# pc_pulse_Express.net
KiCad netlist of a schematic drawn in EAGLE
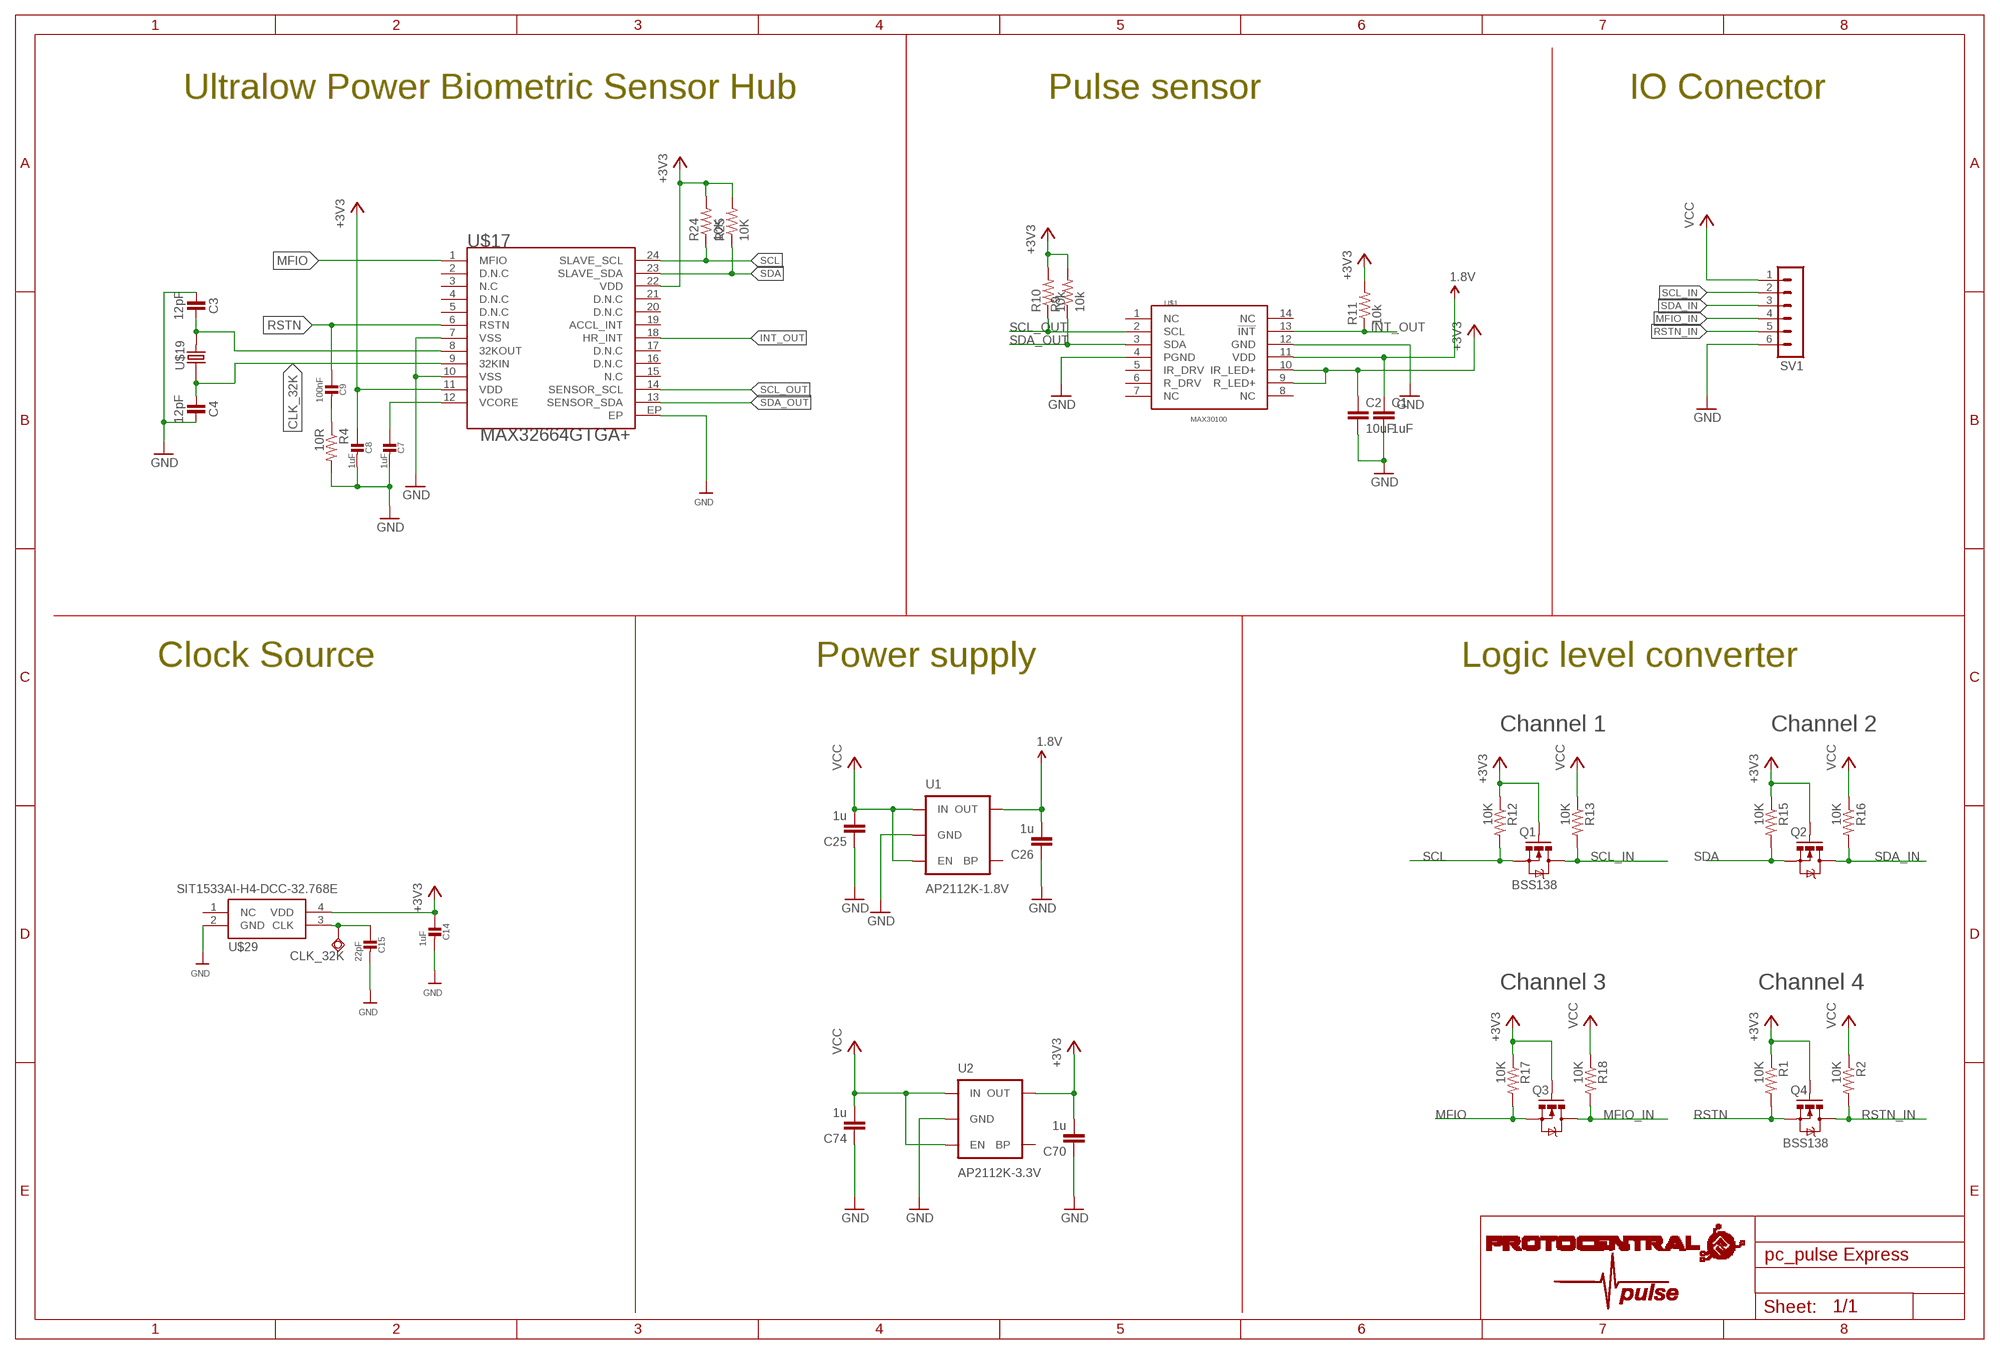
[diagram p0: schematic, sheet 1]

(export (version "E")
  (design (tool "Eeschema 10.0.6"))
  (components
    (comp (ref "C1")
      (value "1uF")
      (footprint "eagle-import:C0402")
      (libsource (lib "eagle-import") (part "rcl_334_C-EUC0402"))
    )
    (comp (ref "C2")
      (value "10uF")
      (footprint "eagle-import:C0402")
      (libsource (lib "eagle-import") (part "rcl_334_C-EUC0402"))
    )
    (comp (ref "C3")
      (value "12pF")
      (footprint "eagle-import:C0402")
      (libsource (lib "eagle-import") (part "CAPACITORS-0402"))
    )
    (comp (ref "C4")
      (value "12pF")
      (footprint "eagle-import:C0402")
      (libsource (lib "eagle-import") (part "CAPACITORS-0402"))
    )
    (comp (ref "C7")
      (value "1uF")
      (footprint "eagle-import:_0402")
      (libsource (lib "eagle-import") (part "CAP_CERAMIC_0402"))
    )
    (comp (ref "C8")
      (value "1uF")
      (footprint "eagle-import:_0402")
      (libsource (lib "eagle-import") (part "CAP_CERAMIC_0402"))
    )
    (comp (ref "C9")
      (value "100nF")
      (footprint "eagle-import:_0402")
      (libsource (lib "eagle-import") (part "CAP_CERAMIC_0402"))
    )
    (comp (ref "C14")
      (value "1uF")
      (footprint "eagle-import:_0402")
      (libsource (lib "eagle-import") (part "CAP_CERAMIC_0402"))
    )
    (comp (ref "C15")
      (value "22pF")
      (footprint "eagle-import:_0402")
      (libsource (lib "eagle-import") (part "CAP_CERAMIC_0402"))
    )
    (comp (ref "C25")
      (value "1u")
      (footprint "eagle-import:C0402")
      (libsource (lib "eagle-import") (part "rcl_334_C-EUC0402"))
    )
    (comp (ref "C26")
      (value "1u")
      (footprint "eagle-import:C0402")
      (libsource (lib "eagle-import") (part "rcl_334_C-EUC0402"))
    )
    (comp (ref "C70")
      (value "1u")
      (footprint "eagle-import:C0402")
      (libsource (lib "eagle-import") (part "C-EUC0402"))
    )
    (comp (ref "C74")
      (value "1u")
      (footprint "eagle-import:C0402")
      (libsource (lib "eagle-import") (part "C-EUC0402"))
    )
    (comp (ref "Q1")
      (value "BSS138")
      (footprint "eagle-import:SOT23-3")
      (libsource (lib "eagle-import") (part "MOSFET-NCHANNELSMD"))
    )
    (comp (ref "Q2")
      (value "BSS138")
      (footprint "eagle-import:SOT23-3")
      (libsource (lib "eagle-import") (part "MOSFET-NCHANNELSMD"))
    )
    (comp (ref "Q3")
      (value "BSS138")
      (footprint "eagle-import:SOT23-3")
      (libsource (lib "eagle-import") (part "MOSFET-NCHANNELSMD"))
    )
    (comp (ref "Q4")
      (value "BSS138")
      (footprint "eagle-import:SOT23-3")
      (libsource (lib "eagle-import") (part "MOSFET-NCHANNELSMD"))
    )
    (comp (ref "R1")
      (value "10K")
      (footprint "eagle-import:0402-RES")
      (libsource (lib "eagle-import") (part "RESISTOR0402-RES"))
    )
    (comp (ref "R2")
      (value "10K")
      (footprint "eagle-import:0402-RES")
      (libsource (lib "eagle-import") (part "RESISTOR0402-RES"))
    )
    (comp (ref "R4")
      (value "10R")
      (footprint "eagle-import:0402-RES")
      (libsource (lib "eagle-import") (part "RESISTOR0402-RES"))
    )
    (comp (ref "R9")
      (value "10k")
      (footprint "eagle-import:R0402")
      (libsource (lib "eagle-import") (part "R-US_R0402"))
    )
    (comp (ref "R10")
      (value "10k")
      (footprint "eagle-import:R0402")
      (libsource (lib "eagle-import") (part "R-US_R0402"))
    )
    (comp (ref "R11")
      (value "10k")
      (footprint "eagle-import:R0402")
      (libsource (lib "eagle-import") (part "R-US_R0402"))
    )
    (comp (ref "R12")
      (value "10K")
      (footprint "eagle-import:0402-RES")
      (libsource (lib "eagle-import") (part "RESISTOR0402-RES"))
    )
    (comp (ref "R13")
      (value "10K")
      (footprint "eagle-import:0402-RES")
      (libsource (lib "eagle-import") (part "RESISTOR0402-RES"))
    )
    (comp (ref "R15")
      (value "10K")
      (footprint "eagle-import:0402-RES")
      (libsource (lib "eagle-import") (part "RESISTOR0402-RES"))
    )
    (comp (ref "R16")
      (value "10K")
      (footprint "eagle-import:0402-RES")
      (libsource (lib "eagle-import") (part "RESISTOR0402-RES"))
    )
    (comp (ref "R17")
      (value "10K")
      (footprint "eagle-import:0402-RES")
      (libsource (lib "eagle-import") (part "RESISTOR0402-RES"))
    )
    (comp (ref "R18")
      (value "10K")
      (footprint "eagle-import:0402-RES")
      (libsource (lib "eagle-import") (part "RESISTOR0402-RES"))
    )
    (comp (ref "R24")
      (value "10K")
      (footprint "eagle-import:0402-RES")
      (libsource (lib "eagle-import") (part "RESISTOR0402-RES"))
    )
    (comp (ref "R25")
      (value "10K")
      (footprint "eagle-import:0402-RES")
      (libsource (lib "eagle-import") (part "RESISTOR0402-RES"))
    )
    (comp (ref "SV1")
      (value "MA06-1")
      (footprint "eagle-import:MA06-1")
      (libsource (lib "eagle-import") (part "MA06-1"))
    )
    (comp (ref "SWIO1")
      (value "TPSQTP11R")
      (footprint "eagle-import:TP11R")
      (libsource (lib "eagle-import") (part "TPSQTP11R"))
    )
    (comp (ref "U$1")
      (value "MAX30100")
      (footprint "eagle-import:OESIP-14")
      (libsource (lib "eagle-import") (part "MAX30100"))
    )
    (comp (ref "U$3")
      (value "PROTY_LOGO_WITH_TEXT")
      (footprint "eagle-import:PROTY_WITH_TEXT")
      (libsource (lib "eagle-import") (part "PROTY_LOGO_WITH_TEXT"))
    )
    (comp (ref "U$4")
      (value "PULSE")
      (footprint "eagle-import:PULSESMALL")
      (libsource (lib "eagle-import") (part "PULSE"))
    )
    (comp (ref "U$17")
      (value "MAX32664GTGA+")
      (footprint "eagle-import:TQFN-24L")
      (libsource (lib "eagle-import") (part "MAX32664GTGA+"))
    )
    (comp (ref "U$19")
      (value "520-327-12.5-34B(32.768KHZ)")
      (footprint "eagle-import:ECX-31B")
      (libsource (lib "eagle-import") (part "ECS-X-34B"))
    )
    (comp (ref "U$29")
      (value "SIT1533AI-H4-DCC-32.768E")
      (footprint "eagle-import:SIT1533")
      (libsource (lib "eagle-import") (part "SIT1533AI-H4-DCC-32.768E"))
    )
    (comp (ref "U1")
      (value "AP2112K-1.8V")
      (footprint "eagle-import:SOT23-5")
      (libsource (lib "eagle-import") (part "V_REG_LDOSMD"))
    )
    (comp (ref "U2")
      (value "AP2112K-3.3V")
      (footprint "eagle-import:SOT23-5")
      (libsource (lib "eagle-import") (part "V_REG_LDOSMD"))
    )
  )
  (nets
    (net (code "1") (name "+3V3") (class "Default")
      (node (ref "C14") (pin "1") (pinfunction "1_1") (pintype "passive"))
      (node (ref "C2") (pin "1") (pinfunction "1_1") (pintype "passive"))
      (node (ref "C70") (pin "2") (pinfunction "2_2") (pintype "passive"))
      (node (ref "C8") (pin "1") (pinfunction "1_1") (pintype "passive"))
      (node (ref "Q1") (pin "1") (pinfunction "G_1") (pintype "passive"))
      (node (ref "Q2") (pin "1") (pinfunction "G_1") (pintype "passive"))
      (node (ref "Q3") (pin "1") (pinfunction "G_1") (pintype "passive"))
      (node (ref "Q4") (pin "1") (pinfunction "G_1") (pintype "passive"))
      (node (ref "R1") (pin "1") (pinfunction "1_1") (pintype "passive"))
      (node (ref "R10") (pin "2") (pinfunction "2_2") (pintype "passive"))
      (node (ref "R11") (pin "2") (pinfunction "2_2") (pintype "passive"))
      (node (ref "R12") (pin "1") (pinfunction "1_1") (pintype "passive"))
      (node (ref "R15") (pin "1") (pinfunction "1_1") (pintype "passive"))
      (node (ref "R17") (pin "1") (pinfunction "1_1") (pintype "passive"))
      (node (ref "R24") (pin "2") (pinfunction "2_2") (pintype "passive"))
      (node (ref "R25") (pin "2") (pinfunction "2_2") (pintype "passive"))
      (node (ref "R9") (pin "2") (pinfunction "2_2") (pintype "passive"))
      (node (ref "U$1") (pin "10") (pinfunction "IR_LED+_10") (pintype "bidirectional"))
      (node (ref "U$1") (pin "9") (pinfunction "R_LED+_9") (pintype "bidirectional"))
      (node (ref "U$17") (pin "11") (pinfunction "VDD_11") (pintype "bidirectional"))
      (node (ref "U$17") (pin "22") (pinfunction "VDD_22") (pintype "bidirectional"))
      (node (ref "U$29") (pin "4") (pinfunction "VDD_4") (pintype "bidirectional"))
      (node (ref "U2") (pin "5") (pinfunction "OUT_5") (pintype "passive"))
    )
    (net (code "2") (name "1.8V") (class "Default")
      (node (ref "C1") (pin "1") (pinfunction "1_1") (pintype "passive"))
      (node (ref "C26") (pin "2") (pinfunction "2_2") (pintype "passive"))
      (node (ref "U$1") (pin "11") (pinfunction "VDD_11") (pintype "bidirectional"))
      (node (ref "U1") (pin "5") (pinfunction "OUT_5") (pintype "passive"))
    )
    (net (code "3") (name "CLK_32K") (class "Default")
      (node (ref "C15") (pin "1") (pinfunction "1_1") (pintype "passive"))
      (node (ref "C4") (pin "1") (pinfunction "1_1") (pintype "passive"))
      (node (ref "SWIO1") (pin "TP") (pinfunction "TP_TP") (pintype "input"))
      (node (ref "U$17") (pin "9") (pinfunction "32KIN_9") (pintype "bidirectional"))
      (node (ref "U$19") (pin "P$1") (pinfunction "1_P$1") (pintype "passive"))
      (node (ref "U$29") (pin "3") (pinfunction "CLK_3") (pintype "bidirectional"))
    )
    (net (code "4") (name "GND") (class "Default")
      (node (ref "C1") (pin "2") (pinfunction "2_2") (pintype "passive"))
      (node (ref "C14") (pin "2") (pinfunction "2_2") (pintype "passive"))
      (node (ref "C15") (pin "2") (pinfunction "2_2") (pintype "passive"))
      (node (ref "C2") (pin "2") (pinfunction "2_2") (pintype "passive"))
      (node (ref "C25") (pin "1") (pinfunction "1_1") (pintype "passive"))
      (node (ref "C26") (pin "1") (pinfunction "1_1") (pintype "passive"))
      (node (ref "C3") (pin "1") (pinfunction "1_1") (pintype "passive"))
      (node (ref "C4") (pin "2") (pinfunction "2_2") (pintype "passive"))
      (node (ref "C7") (pin "2") (pinfunction "2_2") (pintype "passive"))
      (node (ref "C70") (pin "1") (pinfunction "1_1") (pintype "passive"))
      (node (ref "C74") (pin "1") (pinfunction "1_1") (pintype "passive"))
      (node (ref "C8") (pin "2") (pinfunction "2_2") (pintype "passive"))
      (node (ref "R4") (pin "2") (pinfunction "2_2") (pintype "passive"))
      (node (ref "SV1") (pin "6") (pinfunction "6_6") (pintype "passive"))
      (node (ref "U$1") (pin "12") (pinfunction "GND_12") (pintype "bidirectional"))
      (node (ref "U$1") (pin "4") (pinfunction "PGND_4") (pintype "bidirectional"))
      (node (ref "U$17") (pin "10") (pinfunction "VSS_10") (pintype "bidirectional"))
      (node (ref "U$17") (pin "7") (pinfunction "VSS_7") (pintype "bidirectional"))
      (node (ref "U$17") (pin "EP") (pinfunction "EP_EP") (pintype "bidirectional"))
      (node (ref "U$29") (pin "2") (pinfunction "GND_2") (pintype "bidirectional"))
      (node (ref "U1") (pin "2") (pinfunction "GND_2") (pintype "input"))
      (node (ref "U2") (pin "2") (pinfunction "GND_2") (pintype "input"))
    )
    (net (code "5") (name "INT_OUT") (class "Default")
      (node (ref "R11") (pin "1") (pinfunction "1_1") (pintype "passive"))
      (node (ref "U$1") (pin "13") (pinfunction "~{INT}_13") (pintype "bidirectional"))
      (node (ref "U$17") (pin "18") (pinfunction "HR_INT_18") (pintype "bidirectional"))
    )
    (net (code "6") (name "MFIO") (class "Default")
      (node (ref "Q3") (pin "2") (pinfunction "S_2") (pintype "passive"))
      (node (ref "R17") (pin "2") (pinfunction "2_2") (pintype "passive"))
      (node (ref "U$17") (pin "1") (pinfunction "MFIO_1") (pintype "bidirectional"))
    )
    (net (code "7") (name "MFIO_IN") (class "Default")
      (node (ref "Q3") (pin "3") (pinfunction "D_3") (pintype "passive"))
      (node (ref "R18") (pin "2") (pinfunction "2_2") (pintype "passive"))
      (node (ref "SV1") (pin "4") (pinfunction "4_4") (pintype "passive"))
    )
    (net (code "8") (name "Net-(C9-Pad2)") (class "Default")
      (node (ref "C9") (pin "2") (pinfunction "2_2") (pintype "passive"))
      (node (ref "R4") (pin "1") (pinfunction "1_1") (pintype "passive"))
    )
    (net (code "9") (name "Net-(U$17-32KOUT)") (class "Default")
      (node (ref "C3") (pin "2") (pinfunction "2_2") (pintype "passive"))
      (node (ref "U$17") (pin "8") (pinfunction "32KOUT_8") (pintype "bidirectional"))
      (node (ref "U$19") (pin "P$2") (pinfunction "2_P$2") (pintype "passive"))
    )
    (net (code "10") (name "Net-(U$17-VCORE)") (class "Default")
      (node (ref "C7") (pin "1") (pinfunction "1_1") (pintype "passive"))
      (node (ref "U$17") (pin "12") (pinfunction "VCORE_12") (pintype "bidirectional"))
    )
    (net (code "11") (name "RSTN") (class "Default")
      (node (ref "C9") (pin "1") (pinfunction "1_1") (pintype "passive"))
      (node (ref "Q4") (pin "2") (pinfunction "S_2") (pintype "passive"))
      (node (ref "R1") (pin "2") (pinfunction "2_2") (pintype "passive"))
      (node (ref "U$17") (pin "6") (pinfunction "RSTN_6") (pintype "bidirectional"))
    )
    (net (code "12") (name "RSTN_IN") (class "Default")
      (node (ref "Q4") (pin "3") (pinfunction "D_3") (pintype "passive"))
      (node (ref "R2") (pin "2") (pinfunction "2_2") (pintype "passive"))
      (node (ref "SV1") (pin "5") (pinfunction "5_5") (pintype "passive"))
    )
    (net (code "13") (name "SCL") (class "Default")
      (node (ref "Q1") (pin "2") (pinfunction "S_2") (pintype "passive"))
      (node (ref "R12") (pin "2") (pinfunction "2_2") (pintype "passive"))
      (node (ref "R24") (pin "1") (pinfunction "1_1") (pintype "passive"))
      (node (ref "U$17") (pin "24") (pinfunction "SLAVE_SCL_24") (pintype "bidirectional"))
    )
    (net (code "14") (name "SCL_IN") (class "Default")
      (node (ref "Q1") (pin "3") (pinfunction "D_3") (pintype "passive"))
      (node (ref "R13") (pin "2") (pinfunction "2_2") (pintype "passive"))
      (node (ref "SV1") (pin "2") (pinfunction "2_2") (pintype "passive"))
    )
    (net (code "15") (name "SCL_OUT") (class "Default")
      (node (ref "R10") (pin "1") (pinfunction "1_1") (pintype "passive"))
      (node (ref "U$1") (pin "2") (pinfunction "SCL_2") (pintype "bidirectional"))
      (node (ref "U$17") (pin "14") (pinfunction "SENSOR_SCL_14") (pintype "bidirectional"))
    )
    (net (code "16") (name "SDA") (class "Default")
      (node (ref "Q2") (pin "2") (pinfunction "S_2") (pintype "passive"))
      (node (ref "R15") (pin "2") (pinfunction "2_2") (pintype "passive"))
      (node (ref "R25") (pin "1") (pinfunction "1_1") (pintype "passive"))
      (node (ref "U$17") (pin "23") (pinfunction "SLAVE_SDA_23") (pintype "bidirectional"))
    )
    (net (code "17") (name "SDA_IN") (class "Default")
      (node (ref "Q2") (pin "3") (pinfunction "D_3") (pintype "passive"))
      (node (ref "R16") (pin "2") (pinfunction "2_2") (pintype "passive"))
      (node (ref "SV1") (pin "3") (pinfunction "3_3") (pintype "passive"))
    )
    (net (code "18") (name "SDA_OUT") (class "Default")
      (node (ref "R9") (pin "1") (pinfunction "1_1") (pintype "passive"))
      (node (ref "U$1") (pin "3") (pinfunction "SDA_3") (pintype "bidirectional"))
      (node (ref "U$17") (pin "13") (pinfunction "SENSOR_SDA_13") (pintype "bidirectional"))
    )
    (net (code "19") (name "VCC") (class "Default")
      (node (ref "C25") (pin "2") (pinfunction "2_2") (pintype "passive"))
      (node (ref "C74") (pin "2") (pinfunction "2_2") (pintype "passive"))
      (node (ref "R13") (pin "1") (pinfunction "1_1") (pintype "passive"))
      (node (ref "R16") (pin "1") (pinfunction "1_1") (pintype "passive"))
      (node (ref "R18") (pin "1") (pinfunction "1_1") (pintype "passive"))
      (node (ref "R2") (pin "1") (pinfunction "1_1") (pintype "passive"))
      (node (ref "SV1") (pin "1") (pinfunction "1_1") (pintype "passive"))
      (node (ref "U1") (pin "1") (pinfunction "IN_1") (pintype "input"))
      (node (ref "U1") (pin "3") (pinfunction "EN_3") (pintype "input"))
      (node (ref "U2") (pin "1") (pinfunction "IN_1") (pintype "input"))
      (node (ref "U2") (pin "3") (pinfunction "EN_3") (pintype "input"))
    )
    (net (code "20") (name "unconnected-(U$1-IR_DRV-Pad5)") (class "Default")
      (node (ref "U$1") (pin "5") (pinfunction "IR_DRV_5") (pintype "bidirectional"))
    )
    (net (code "21") (name "unconnected-(U$1-NC-Pad1)") (class "Default")
      (node (ref "U$1") (pin "1") (pinfunction "NC_1") (pintype "bidirectional"))
    )
    (net (code "22") (name "unconnected-(U$1-NC-Pad7)") (class "Default")
      (node (ref "U$1") (pin "7") (pinfunction "NC_7") (pintype "bidirectional"))
    )
    (net (code "23") (name "unconnected-(U$1-NC-Pad8)") (class "Default")
      (node (ref "U$1") (pin "8") (pinfunction "NC_8") (pintype "bidirectional"))
    )
    (net (code "24") (name "unconnected-(U$1-NC-Pad14)") (class "Default")
      (node (ref "U$1") (pin "14") (pinfunction "NC_14") (pintype "bidirectional"))
    )
    (net (code "25") (name "unconnected-(U$1-R_DRV-Pad6)") (class "Default")
      (node (ref "U$1") (pin "6") (pinfunction "R_DRV_6") (pintype "bidirectional"))
    )
    (net (code "26") (name "unconnected-(U$17-ACCL_INT-Pad19)") (class "Default")
      (node (ref "U$17") (pin "19") (pinfunction "ACCL_INT_19") (pintype "bidirectional"))
    )
    (net (code "27") (name "unconnected-(U$17-D.N.C-Pad2)") (class "Default")
      (node (ref "U$17") (pin "2") (pinfunction "D.N.C_2") (pintype "bidirectional"))
    )
    (net (code "28") (name "unconnected-(U$17-D.N.C-Pad4)") (class "Default")
      (node (ref "U$17") (pin "4") (pinfunction "D.N.C_4") (pintype "bidirectional"))
    )
    (net (code "29") (name "unconnected-(U$17-D.N.C-Pad5)") (class "Default")
      (node (ref "U$17") (pin "5") (pinfunction "D.N.C_5") (pintype "bidirectional"))
    )
    (net (code "30") (name "unconnected-(U$17-D.N.C-Pad16)") (class "Default")
      (node (ref "U$17") (pin "16") (pinfunction "D.N.C_16") (pintype "bidirectional"))
    )
    (net (code "31") (name "unconnected-(U$17-D.N.C-Pad17)") (class "Default")
      (node (ref "U$17") (pin "17") (pinfunction "D.N.C_17") (pintype "bidirectional"))
    )
    (net (code "32") (name "unconnected-(U$17-D.N.C-Pad20)") (class "Default")
      (node (ref "U$17") (pin "20") (pinfunction "D.N.C_20") (pintype "bidirectional"))
    )
    (net (code "33") (name "unconnected-(U$17-D.N.C-Pad21)") (class "Default")
      (node (ref "U$17") (pin "21") (pinfunction "D.N.C_21") (pintype "bidirectional"))
    )
    (net (code "34") (name "unconnected-(U$17-N.C-Pad3)") (class "Default")
      (node (ref "U$17") (pin "3") (pinfunction "N.C_3") (pintype "bidirectional"))
    )
    (net (code "35") (name "unconnected-(U$17-N.C-Pad15)") (class "Default")
      (node (ref "U$17") (pin "15") (pinfunction "N.C_15") (pintype "bidirectional"))
    )
    (net (code "36") (name "unconnected-(U$29-NC-Pad1)") (class "Default")
      (node (ref "U$29") (pin "1") (pinfunction "NC_1") (pintype "bidirectional"))
    )
    (net (code "37") (name "unconnected-(U1-BP-Pad4)") (class "Default")
      (node (ref "U1") (pin "4") (pinfunction "BP_4") (pintype "input"))
    )
    (net (code "38") (name "unconnected-(U2-BP-Pad4)") (class "Default")
      (node (ref "U2") (pin "4") (pinfunction "BP_4") (pintype "input"))
    )
  )
)
